# SH3_-_LEVEL_SHIFTER.net
KiCad netlist of a schematic drawn in Altium Designer
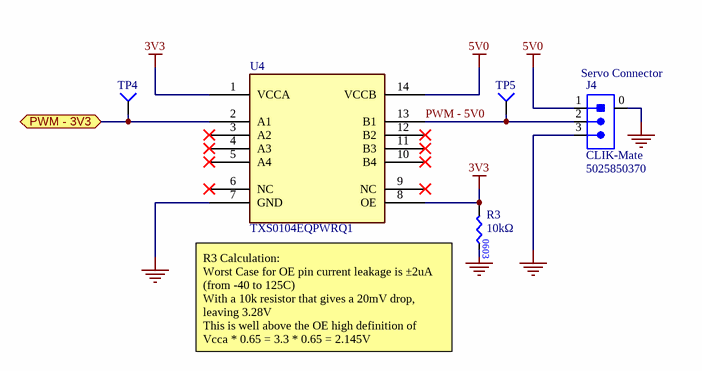
[diagram p0: SH3 - LEVEL SHIFTER.SchDoc]

(export (version "E")
  (design (tool "Eeschema 10.0.6"))
  (components
    (comp (ref "J4")
      (value "CON_3M_SM_RA")
      (footprint "MOLEX-5025850370")
      (description "CONN RCPT 3POS 0.059 TIN SMD R/A")
      (fields (field (name "FAMILY") "CLIK-Mate") (field (name "MANUFACTURER PART NUMBER 1") "5025850370"))
      (libsource (lib "UWRT_Schematic_Library_2020") (part "CON_3M_SM_RA"))
    )
    (comp (ref "R3")
      (value "10kΩ")
      (footprint "RES0603")
      (description "RES 10K OHM 5% 1/10W 0603")
      (fields (field (name "Comment") "RES_10kΩ_0603_5%"))
      (libsource (lib "UWRT_Schematic_Library_2020") (part "RES_10kΩ_0603_5%"))
    )
    (comp (ref "TP4")
      (value "TESTPOINT_SMD_LOOP")
      (footprint "S1751-46R")
      (description "PC TEST POINT SMD")
      (libsource (lib "UWRT_Schematic_Library_2020") (part "TESTPOINT_SMD_LOOP"))
    )
    (comp (ref "TP5")
      (value "TESTPOINT_SMD_LOOP")
      (footprint "S1751-46R")
      (description "PC TEST POINT SMD")
      (libsource (lib "UWRT_Schematic_Library_2020") (part "TESTPOINT_SMD_LOOP"))
    )
    (comp (ref "U4")
      (value "IC_LVL_SHIFTER_4_CH")
      (footprint "UWRT_Footprint_Library_2020:TXS0104EQPWRQ1")
      (description "IC BIDIRECTIONAL LEVEL SHIFTER 4 CHANNEL 14TSSOP")
      (fields (field (name "MANUFACTURER PART NUMBER 1") "TXS0104EQPWRQ1"))
      (libsource (lib "UWRT_Schematic_Library_2020") (part "IC_LVL_SHIFTER_4_CH"))
    )
  )
  (nets
    (net (code "1") (name "/PWM - 3V3") (class "Default")
      (node (ref "TP4") (pin "1") (pinfunction "=value_1") (pintype "passive"))
      (node (ref "U4") (pin "2") (pinfunction "A1_2") (pintype "passive"))
    )
    (net (code "2") (name "/PWM - 5V0") (class "Default")
      (node (ref "J4") (pin "2") (pinfunction "2_2") (pintype "passive"))
      (node (ref "TP5") (pin "1") (pinfunction "=value_1") (pintype "passive"))
      (node (ref "U4") (pin "13") (pinfunction "B1_13") (pintype "passive"))
    )
    (net (code "3") (name "3V3") (class "Default")
      (node (ref "R3") (pin "1") (pinfunction "1_1") (pintype "passive"))
      (node (ref "U4") (pin "1") (pinfunction "VCCA_1") (pintype "passive"))
      (node (ref "U4") (pin "8") (pinfunction "OE_8") (pintype "passive"))
    )
    (net (code "4") (name "5V0") (class "Default")
      (node (ref "J4") (pin "1") (pinfunction "1_1") (pintype "passive"))
      (node (ref "U4") (pin "14") (pinfunction "VCCB_14") (pintype "passive"))
    )
    (net (code "5") (name "GND") (class "Default")
      (node (ref "J4") (pin "0") (pinfunction "0_0") (pintype "passive"))
      (node (ref "J4") (pin "3") (pinfunction "3_3") (pintype "passive"))
      (node (ref "R3") (pin "2") (pinfunction "2_2") (pintype "passive"))
      (node (ref "U4") (pin "7") (pinfunction "GND_7") (pintype "passive"))
    )
    (net (code "6") (name "unconnected-(U4-A2-Pad3)") (class "Default")
      (node (ref "U4") (pin "3") (pinfunction "A2_3") (pintype "passive+no_connect"))
    )
    (net (code "7") (name "unconnected-(U4-A3-Pad4)") (class "Default")
      (node (ref "U4") (pin "4") (pinfunction "A3_4") (pintype "passive+no_connect"))
    )
    (net (code "8") (name "unconnected-(U4-A4-Pad5)") (class "Default")
      (node (ref "U4") (pin "5") (pinfunction "A4_5") (pintype "passive+no_connect"))
    )
    (net (code "9") (name "unconnected-(U4-B2-Pad12)") (class "Default")
      (node (ref "U4") (pin "12") (pinfunction "B2_12") (pintype "passive+no_connect"))
    )
    (net (code "10") (name "unconnected-(U4-B3-Pad11)") (class "Default")
      (node (ref "U4") (pin "11") (pinfunction "B3_11") (pintype "passive+no_connect"))
    )
    (net (code "11") (name "unconnected-(U4-B4-Pad10)") (class "Default")
      (node (ref "U4") (pin "10") (pinfunction "B4_10") (pintype "passive+no_connect"))
    )
    (net (code "12") (name "unconnected-(U4-NC-Pad6)") (class "Default")
      (node (ref "U4") (pin "6") (pinfunction "NC_6") (pintype "passive+no_connect"))
    )
    (net (code "13") (name "unconnected-(U4-NC-Pad9)") (class "Default")
      (node (ref "U4") (pin "9") (pinfunction "NC_9") (pintype "passive+no_connect"))
    )
  )
)
